# POWER_2_5V_3A.net
KiCad netlist of a schematic drawn in Altium Designer
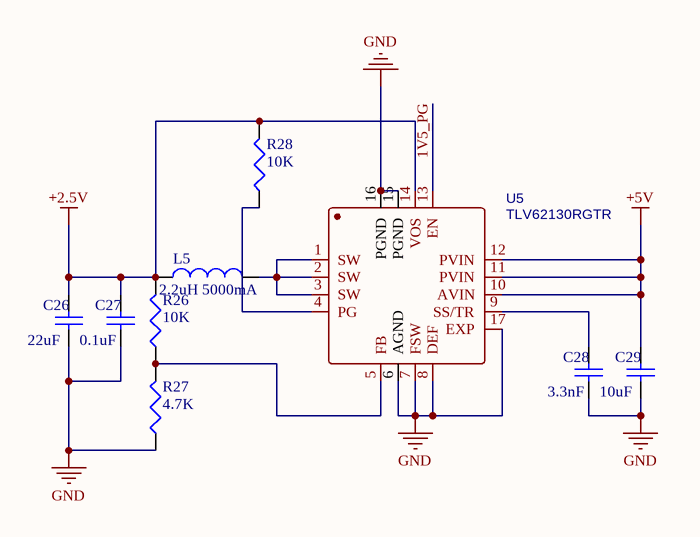
[diagram p0: POWER_2.5V_3A.SchDoc]

(export (version "E")
  (design (tool "Eeschema 10.0.6"))
  (components
    (comp (ref "C26")
      (value "22uF")
      (footprint "C1210")
      (description "Capacitor (Semiconductor SIM Model)")
      (fields (field (name "Comment") "Cap Semi") (field (name "PUBLISHER") "Altium Limited"))
      (libsource (lib "Miscellaneous Devices") (part "Cap Semi"))
    )
    (comp (ref "C27")
      (value "0.1uF")
      (footprint "C1210")
      (description "Capacitor (Semiconductor SIM Model)")
      (fields (field (name "Comment") "Cap Semi") (field (name "PUBLISHER") "Altium Limited"))
      (libsource (lib "Miscellaneous Devices") (part "Cap Semi"))
    )
    (comp (ref "C28")
      (value "3.3nF")
      (footprint "C1210")
      (description "Capacitor (Semiconductor SIM Model)")
      (fields (field (name "Comment") "Cap Semi") (field (name "PUBLISHER") "Altium Limited"))
      (libsource (lib "Miscellaneous Devices") (part "Cap Semi"))
    )
    (comp (ref "C29")
      (value "10uF")
      (footprint "C1210")
      (description "Capacitor (Semiconductor SIM Model)")
      (fields (field (name "Comment") "Cap Semi") (field (name "PUBLISHER") "Altium Limited"))
      (libsource (lib "Miscellaneous Devices") (part "Cap Semi"))
    )
    (comp (ref "L5")
      (value "2.2uH 5000mA")
      (footprint "IND-SMD_L5.5-W5.2")
      (description "Inductor")
      (fields (field (name "PUBLISHER") "Altium Limited"))
      (libsource (lib "Miscellaneous Devices") (part "Inductor"))
    )
    (comp (ref "R26")
      (value "10K")
      (footprint "J1-0603")
      (description "Resistor")
      (fields (field (name "Comment") "Res3") (field (name "PUBLISHER") "Altium Limited"))
      (libsource (lib "Miscellaneous Devices") (part "Res3"))
    )
    (comp (ref "R27")
      (value "4.7K")
      (footprint "J1-0603")
      (description "Resistor")
      (fields (field (name "Comment") "Res3") (field (name "PUBLISHER") "Altium Limited"))
      (libsource (lib "Miscellaneous Devices") (part "Res3"))
    )
    (comp (ref "R28")
      (value "10K")
      (footprint "J1-0603")
      (description "Resistor")
      (fields (field (name "Comment") "Res3") (field (name "PUBLISHER") "Altium Limited"))
      (libsource (lib "Miscellaneous Devices") (part "Res3"))
    )
    (comp (ref "U5")
      (value "TLV62130RGTR")
      (footprint "QFN-16")
      (fields (field (name "BOM_SUPPLIER PART") "C122479") (field (name "CONTRIBUTOR") "LCSC"))
      (libsource (lib "power_chip") (part "TLV62130RGTR"))
    )
  )
  (nets
    (net (code "1") (name "+2.5V") (class "Default")
      (node (ref "C26") (pin "2") (pinfunction "2_2") (pintype "passive"))
      (node (ref "C27") (pin "2") (pinfunction "2_2") (pintype "passive"))
      (node (ref "L5") (pin "1") (pinfunction "1_1") (pintype "passive"))
      (node (ref "R26") (pin "2") (pinfunction "2_2") (pintype "passive"))
      (node (ref "R28") (pin "2") (pinfunction "2_2") (pintype "passive"))
      (node (ref "U5") (pin "14") (pinfunction "VOS_14") (pintype "passive"))
    )
    (net (code "2") (name "+5V") (class "Default")
      (node (ref "C29") (pin "2") (pinfunction "2_2") (pintype "passive"))
      (node (ref "U5") (pin "10") (pinfunction "AVIN_10") (pintype "passive"))
      (node (ref "U5") (pin "11") (pinfunction "PVIN_11") (pintype "passive"))
      (node (ref "U5") (pin "12") (pinfunction "PVIN_12") (pintype "passive"))
    )
    (net (code "3") (name "/1V5_PG") (class "Default")
      (node (ref "U5") (pin "13") (pinfunction "EN_13") (pintype "passive"))
    )
    (net (code "4") (name "GND") (class "Default")
      (node (ref "C26") (pin "1") (pinfunction "1_1") (pintype "passive"))
      (node (ref "C27") (pin "1") (pinfunction "1_1") (pintype "passive"))
      (node (ref "C28") (pin "1") (pinfunction "1_1") (pintype "passive"))
      (node (ref "C29") (pin "1") (pinfunction "1_1") (pintype "passive"))
      (node (ref "R27") (pin "1") (pinfunction "1_1") (pintype "passive"))
      (node (ref "U5") (pin "15") (pinfunction "PGND_15") (pintype "passive"))
      (node (ref "U5") (pin "16") (pinfunction "PGND_16") (pintype "passive"))
      (node (ref "U5") (pin "17") (pinfunction "EXP_17") (pintype "passive"))
      (node (ref "U5") (pin "6") (pinfunction "AGND_6") (pintype "passive"))
      (node (ref "U5") (pin "7") (pinfunction "FSW_7") (pintype "passive"))
      (node (ref "U5") (pin "8") (pinfunction "DEF_8") (pintype "passive"))
    )
    (net (code "5") (name "Net-(L5-Pad2)") (class "Default")
      (node (ref "L5") (pin "2") (pinfunction "2_2") (pintype "passive"))
      (node (ref "U5") (pin "1") (pinfunction "SW_1") (pintype "passive"))
      (node (ref "U5") (pin "2") (pinfunction "SW_2") (pintype "passive"))
      (node (ref "U5") (pin "3") (pinfunction "SW_3") (pintype "passive"))
    )
    (net (code "6") (name "Net-(U5-FB)") (class "Default")
      (node (ref "R26") (pin "1") (pinfunction "1_1") (pintype "passive"))
      (node (ref "R27") (pin "2") (pinfunction "2_2") (pintype "passive"))
      (node (ref "U5") (pin "5") (pinfunction "FB_5") (pintype "passive"))
    )
    (net (code "7") (name "Net-(U5-PG)") (class "Default")
      (node (ref "R28") (pin "1") (pinfunction "1_1") (pintype "passive"))
      (node (ref "U5") (pin "4") (pinfunction "PG_4") (pintype "passive"))
    )
    (net (code "8") (name "Net-(U5-SS{slash}TR)") (class "Default")
      (node (ref "C28") (pin "2") (pinfunction "2_2") (pintype "passive"))
      (node (ref "U5") (pin "9") (pinfunction "SS/TR_9") (pintype "passive"))
    )
  )
)
